# PIC18F56Q83.net
KiCad netlist of a schematic drawn in Altium Designer
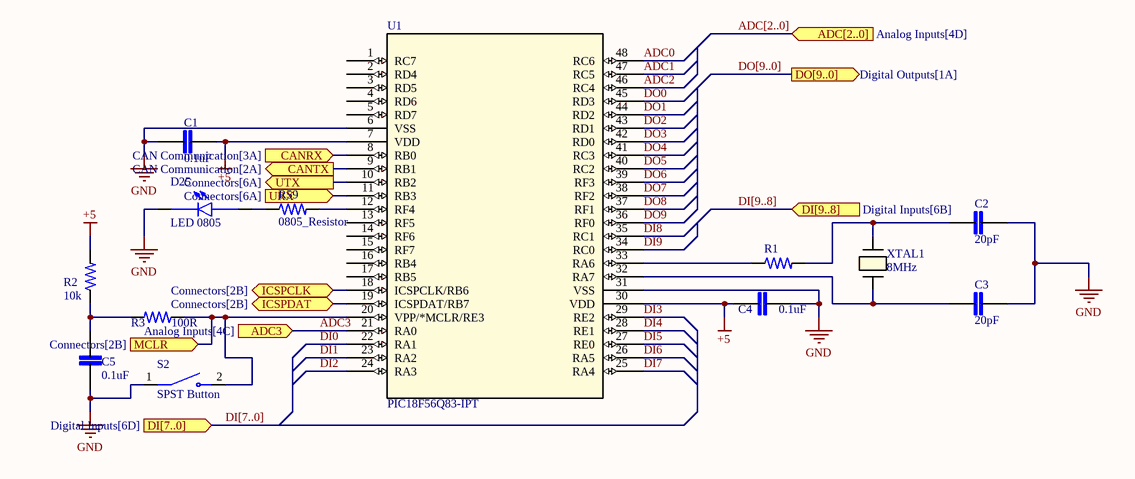
[diagram p0: PIC18F56Q83.SchDoc]

(export (version "E")
  (design (tool "Eeschema 10.0.6"))
  (components
    (comp (ref "C1")
      (value "0.1uF")
      (footprint "0805")
      (fields (field (name "MP") "LD051A121KAB2A") (field (name "MF") "AVX"))
      (libsource (lib "") (part "0805_Capacitor_2"))
    )
    (comp (ref "C2")
      (value "20pF")
      (footprint "0805")
      (fields (field (name "MP") "LD051A121KAB2A") (field (name "MF") "AVX"))
      (libsource (lib "Capacitors SMD") (part "0805_Capacitor"))
    )
    (comp (ref "C3")
      (value "20pF")
      (footprint "0805")
      (fields (field (name "MP") "LD051A121KAB2A") (field (name "MF") "AVX"))
      (libsource (lib "Capacitors SMD") (part "0805_Capacitor"))
    )
    (comp (ref "C4")
      (value "0.1uF")
      (footprint "0805")
      (fields (field (name "MP") "LD051A121KAB2A") (field (name "MF") "AVX"))
      (libsource (lib "Capacitors SMD") (part "0805_Capacitor"))
    )
    (comp (ref "C5")
      (value "0.1uF")
      (footprint "0805")
      (fields (field (name "MP") "LD051A121KAB2A") (field (name "MF") "AVX"))
      (libsource (lib "") (part "0805_Capacitor_1"))
    )
    (comp (ref "D25")
      (value "LED 0805")
      (footprint "LED 0805")
      (description "LED Uni-Color Green 4-Pin Chip 0805 T/R")
      (fields (field (name "MP") "597-3305-607F"))
      (libsource (lib "LEDs SMD") (part "LED 0805"))
    )
    (comp (ref "R1")
      (value "0805_Resistor")
      (footprint "0805")
      (fields
        (field (name "MP") "2-2176053-0")
        (field (name "TOLERANCE") "1%")
        (field (name "MF") "TE Connectivity")
      )
      (libsource (lib "Resistors SMD") (part "0805_Resistor"))
    )
    (comp (ref "R2")
      (value "10k")
      (footprint "0805")
      (fields
        (field (name "MP") "2-2176053-0")
        (field (name "TOLERANCE") "1%")
        (field (name "MF") "TE Connectivity")
      )
      (libsource (lib "Resistors SMD") (part "0805_Resistor"))
    )
    (comp (ref "R3")
      (value "100R")
      (footprint "0805")
      (fields
        (field (name "MP") "2-2176053-0")
        (field (name "TOLERANCE") "1%")
        (field (name "MF") "TE Connectivity")
      )
      (libsource (lib "Resistors SMD") (part "0805_Resistor"))
    )
    (comp (ref "R59")
      (value "0805_Resistor")
      (footprint "0805")
      (fields
        (field (name "MP") "2-2176053-0")
        (field (name "TOLERANCE") "1%")
        (field (name "MF") "TE Connectivity")
      )
      (libsource (lib "Resistors SMD") (part "0805_Resistor"))
    )
    (comp (ref "S2")
      (value "SPST Button")
      (footprint "Button SMD:SPST Button")
      (description "3mmX6mm")
      (fields (field (name "MP") "B3U-1000P"))
      (libsource (lib "Button SMD") (part "SPST Button"))
    )
    (comp (ref "U1")
      (value "PIC18F56Q83-IPT")
      (footprint "PIC18F56Q83-IPT")
      (description "No Description Available")
      (libsource (lib "Microcontrollers") (part "PIC18F56Q83-IPT"))
    )
    (comp (ref "XTAL1")
      (value "8MHz")
      (footprint "Crystal 8MHz")
      (description "5032")
      (fields
        (field (name "MANUFACTURER_PART_NUMBER") "SC32A-12.5PF20PPM")
        (field (name "COPYRIGHT") "Copyright (C) 2024 Ultra Librarian. All rights reserved.")
      )
      (libsource (lib "Crystals SMD") (part "Crystal 8MHz"))
    )
  )
  (nets
    (net (code "1") (name "+5") (class "Default")
      (node (ref "C1") (pin "1") (pinfunction "1_1") (pintype "passive"))
      (node (ref "C4") (pin "1") (pinfunction "1_1") (pintype "passive"))
      (node (ref "R2") (pin "2") (pinfunction "2_2") (pintype "passive"))
      (node (ref "U1") (pin "30") (pinfunction "VDD_30") (pintype "power_in"))
      (node (ref "U1") (pin "7") (pinfunction "VDD_7") (pintype "power_in"))
    )
    (net (code "2") (name "/ADC0") (class "Default")
      (node (ref "U1") (pin "48") (pinfunction "RC6_48") (pintype "bidirectional"))
    )
    (net (code "3") (name "/ADC1") (class "Default")
      (node (ref "U1") (pin "47") (pinfunction "RC5_47") (pintype "bidirectional"))
    )
    (net (code "4") (name "/ADC2") (class "Default")
      (node (ref "U1") (pin "46") (pinfunction "RC4_46") (pintype "bidirectional"))
    )
    (net (code "5") (name "/ADC3") (class "Default")
      (node (ref "U1") (pin "21") (pinfunction "RA0_21") (pintype "bidirectional"))
    )
    (net (code "7") (name "/CANRX") (class "Default")
      (node (ref "U1") (pin "8") (pinfunction "RB0_8") (pintype "bidirectional"))
    )
    (net (code "8") (name "/CANTX") (class "Default")
      (node (ref "U1") (pin "9") (pinfunction "RB1_9") (pintype "bidirectional"))
    )
    (net (code "9") (name "/DI0") (class "Default")
      (node (ref "U1") (pin "22") (pinfunction "RA1_22") (pintype "bidirectional"))
    )
    (net (code "10") (name "/DI1") (class "Default")
      (node (ref "U1") (pin "23") (pinfunction "RA2_23") (pintype "bidirectional"))
    )
    (net (code "11") (name "/DI2") (class "Default")
      (node (ref "U1") (pin "24") (pinfunction "RA3_24") (pintype "bidirectional"))
    )
    (net (code "12") (name "/DI3") (class "Default")
      (node (ref "U1") (pin "29") (pinfunction "RE2_29") (pintype "bidirectional"))
    )
    (net (code "13") (name "/DI4") (class "Default")
      (node (ref "U1") (pin "28") (pinfunction "RE1_28") (pintype "bidirectional"))
    )
    (net (code "14") (name "/DI5") (class "Default")
      (node (ref "U1") (pin "27") (pinfunction "RE0_27") (pintype "bidirectional"))
    )
    (net (code "15") (name "/DI6") (class "Default")
      (node (ref "U1") (pin "26") (pinfunction "RA5_26") (pintype "bidirectional"))
    )
    (net (code "16") (name "/DI7") (class "Default")
      (node (ref "U1") (pin "25") (pinfunction "RA4_25") (pintype "bidirectional"))
    )
    (net (code "17") (name "/DI8") (class "Default")
      (node (ref "U1") (pin "35") (pinfunction "RC1_35") (pintype "bidirectional"))
    )
    (net (code "18") (name "/DI9") (class "Default")
      (node (ref "U1") (pin "34") (pinfunction "RC0_34") (pintype "bidirectional"))
    )
    (net (code "21") (name "/DO0") (class "Default")
      (node (ref "U1") (pin "45") (pinfunction "RD3_45") (pintype "bidirectional"))
    )
    (net (code "22") (name "/DO1") (class "Default")
      (node (ref "U1") (pin "44") (pinfunction "RD2_44") (pintype "bidirectional"))
    )
    (net (code "23") (name "/DO2") (class "Default")
      (node (ref "U1") (pin "43") (pinfunction "RD1_43") (pintype "bidirectional"))
    )
    (net (code "24") (name "/DO3") (class "Default")
      (node (ref "U1") (pin "42") (pinfunction "RD0_42") (pintype "bidirectional"))
    )
    (net (code "25") (name "/DO4") (class "Default")
      (node (ref "U1") (pin "41") (pinfunction "RC3_41") (pintype "bidirectional"))
    )
    (net (code "26") (name "/DO5") (class "Default")
      (node (ref "U1") (pin "40") (pinfunction "RC2_40") (pintype "bidirectional"))
    )
    (net (code "27") (name "/DO6") (class "Default")
      (node (ref "U1") (pin "39") (pinfunction "RF3_39") (pintype "bidirectional"))
    )
    (net (code "28") (name "/DO7") (class "Default")
      (node (ref "U1") (pin "38") (pinfunction "RF2_38") (pintype "bidirectional"))
    )
    (net (code "29") (name "/DO8") (class "Default")
      (node (ref "U1") (pin "37") (pinfunction "RF1_37") (pintype "bidirectional"))
    )
    (net (code "30") (name "/DO9") (class "Default")
      (node (ref "U1") (pin "36") (pinfunction "RF0_36") (pintype "bidirectional"))
    )
    (net (code "32") (name "/ICSPCLK") (class "Default")
      (node (ref "U1") (pin "18") (pinfunction "ICSPCLK/RB6_18") (pintype "bidirectional"))
    )
    (net (code "33") (name "/ICSPDAT") (class "Default")
      (node (ref "U1") (pin "19") (pinfunction "ICSPDAT/RB7_19") (pintype "bidirectional"))
    )
    (net (code "34") (name "/MCLR") (class "Default")
      (node (ref "R3") (pin "1") (pinfunction "1_1") (pintype "passive"))
      (node (ref "S2") (pin "2") (pinfunction "2_2") (pintype "passive"))
      (node (ref "U1") (pin "20") (pinfunction "VPP/*MCLR/RE3_20") (pintype "bidirectional"))
    )
    (net (code "35") (name "/URX") (class "Default")
      (node (ref "U1") (pin "11") (pinfunction "RB3_11") (pintype "bidirectional"))
    )
    (net (code "36") (name "/UTX") (class "Default")
      (node (ref "U1") (pin "10") (pinfunction "RB2_10") (pintype "bidirectional"))
    )
    (net (code "37") (name "GND") (class "Default")
      (node (ref "C1") (pin "2") (pinfunction "2_2") (pintype "passive"))
      (node (ref "C2") (pin "2") (pinfunction "2_2") (pintype "passive"))
      (node (ref "C3") (pin "2") (pinfunction "2_2") (pintype "passive"))
      (node (ref "C4") (pin "2") (pinfunction "2_2") (pintype "passive"))
      (node (ref "C5") (pin "1") (pinfunction "1_1") (pintype "passive"))
      (node (ref "D25") (pin "C") (pinfunction "C_C") (pintype "passive"))
      (node (ref "S2") (pin "1") (pinfunction "1_1") (pintype "passive"))
      (node (ref "U1") (pin "31") (pinfunction "VSS_31") (pintype "power_in"))
      (node (ref "U1") (pin "6") (pinfunction "VSS_6") (pintype "power_in"))
    )
    (net (code "38") (name "Net-(C2-Pad1)") (class "Default")
      (node (ref "C2") (pin "1") (pinfunction "1_1") (pintype "passive"))
      (node (ref "R1") (pin "2") (pinfunction "2_2") (pintype "passive"))
      (node (ref "XTAL1") (pin "2") (pinfunction "2_2") (pintype "passive"))
    )
    (net (code "39") (name "Net-(C5-Pad2)") (class "Default")
      (node (ref "C5") (pin "2") (pinfunction "2_2") (pintype "passive"))
      (node (ref "R2") (pin "1") (pinfunction "1_1") (pintype "passive"))
      (node (ref "R3") (pin "2") (pinfunction "2_2") (pintype "passive"))
    )
    (net (code "40") (name "Net-(D25-PadA)") (class "Default")
      (node (ref "D25") (pin "A") (pinfunction "A_A") (pintype "passive"))
      (node (ref "R59") (pin "1") (pinfunction "1_1") (pintype "passive"))
    )
    (net (code "41") (name "Net-(U1-RA6)") (class "Default")
      (node (ref "R1") (pin "1") (pinfunction "1_1") (pintype "passive"))
      (node (ref "U1") (pin "33") (pinfunction "RA6_33") (pintype "bidirectional"))
    )
    (net (code "42") (name "Net-(U1-RA7)") (class "Default")
      (node (ref "C3") (pin "1") (pinfunction "1_1") (pintype "passive"))
      (node (ref "U1") (pin "32") (pinfunction "RA7_32") (pintype "bidirectional"))
      (node (ref "XTAL1") (pin "1") (pinfunction "1_1") (pintype "passive"))
    )
    (net (code "43") (name "Net-(U1-RF4)") (class "Default")
      (node (ref "R59") (pin "2") (pinfunction "2_2") (pintype "passive"))
      (node (ref "U1") (pin "12") (pinfunction "RF4_12") (pintype "bidirectional"))
    )
    (net (code "44") (name "unconnected-(U1-RB4-Pad16)") (class "Default")
      (node (ref "U1") (pin "16") (pinfunction "RB4_16") (pintype "bidirectional"))
    )
    (net (code "45") (name "unconnected-(U1-RB5-Pad17)") (class "Default")
      (node (ref "U1") (pin "17") (pinfunction "RB5_17") (pintype "bidirectional"))
    )
    (net (code "46") (name "unconnected-(U1-RC7-Pad1)") (class "Default")
      (node (ref "U1") (pin "1") (pinfunction "RC7_1") (pintype "bidirectional"))
    )
    (net (code "47") (name "unconnected-(U1-RD4-Pad2)") (class "Default")
      (node (ref "U1") (pin "2") (pinfunction "RD4_2") (pintype "bidirectional"))
    )
    (net (code "48") (name "unconnected-(U1-RD5-Pad3)") (class "Default")
      (node (ref "U1") (pin "3") (pinfunction "RD5_3") (pintype "bidirectional"))
    )
    (net (code "49") (name "unconnected-(U1-RD6-Pad4)") (class "Default")
      (node (ref "U1") (pin "4") (pinfunction "RD6_4") (pintype "bidirectional"))
    )
    (net (code "50") (name "unconnected-(U1-RD7-Pad5)") (class "Default")
      (node (ref "U1") (pin "5") (pinfunction "RD7_5") (pintype "bidirectional"))
    )
    (net (code "51") (name "unconnected-(U1-RF5-Pad13)") (class "Default")
      (node (ref "U1") (pin "13") (pinfunction "RF5_13") (pintype "bidirectional"))
    )
    (net (code "52") (name "unconnected-(U1-RF6-Pad14)") (class "Default")
      (node (ref "U1") (pin "14") (pinfunction "RF6_14") (pintype "bidirectional"))
    )
    (net (code "53") (name "unconnected-(U1-RF7-Pad15)") (class "Default")
      (node (ref "U1") (pin "15") (pinfunction "RF7_15") (pintype "bidirectional"))
    )
  )
)
